# MP2019_LDO_5V.net
KiCad netlist of a schematic drawn in Altium Designer
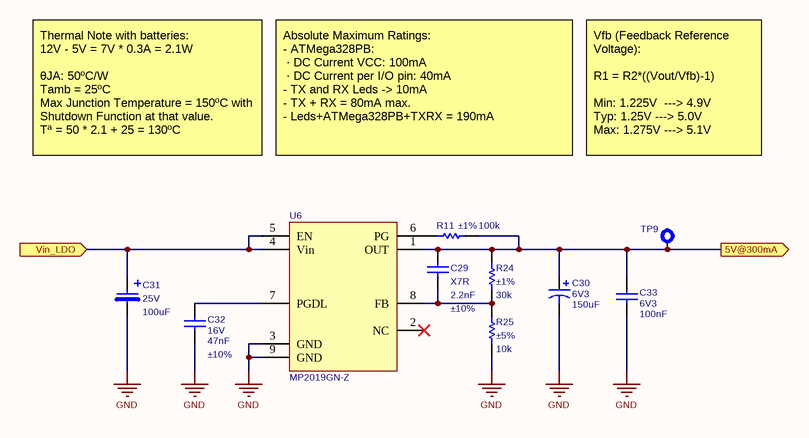
[diagram p0: MP2019_LDO_5V.SchDoc]

(export (version "E")
  (design (tool "Eeschema 10.0.6"))
  (components
    (comp (ref "C29")
      (value "C0402_2.2nF_16V_±10%")
      (footprint "C0402")
      (fields
        (field (name "DIELECTRIC") "X7R")
        (field (name "VOLTAGE") "16V")
        (field (name "CAPACITANCE") "2.2nF")
        (field (name "TOLERANCE") "±10%")
        (field (name "MANUFACTURER") "Kemet")
      )
      (libsource (lib "BQ Vault") (part "Capacitor"))
    )
    (comp (ref "C30")
      (value "150uF_6V3_±20%")
      (footprint "CASE_B_3528-1411")
      (fields
        (field (name "VOLTAGE") "6V3")
        (field (name "CAPACITANCE") "150uF")
        (field (name "TOLERANCE") "±20%")
        (field (name "MANUFACTURER") "Vishay")
      )
      (libsource (lib "BQ Vault") (part "Tantalum"))
    )
    (comp (ref "C31")
      (value "Cap_Al_100uF_25V")
      (footprint "CASE_D_7.7")
      (fields
        (field (name "VOLTAGE") "25V")
        (field (name "CAPACITANCE") "100uF")
        (field (name "MANUFACTURER") "Panasonic")
      )
      (libsource (lib "BQ Vault") (part "Electrolytic"))
    )
    (comp (ref "C32")
      (value "C0402_47nF_16V_±10%")
      (footprint "C0402")
      (fields
        (field (name "VOLTAGE") "16V")
        (field (name "CAPACITANCE") "47nF")
        (field (name "TOLERANCE") "±10%")
        (field (name "MANUFACTURER") "Kemet")
      )
      (libsource (lib "BQ Vault") (part "Capacitor"))
    )
    (comp (ref "C33")
      (value "C0402_100nF_6V3_±10%")
      (footprint "C0402")
      (fields
        (field (name "VOLTAGE") "6V3")
        (field (name "CAPACITANCE") "100nF")
        (field (name "TOLERANCE") "±10%")
        (field (name "MANUFACTURER") "Kemet")
      )
      (libsource (lib "BQ Vault") (part "Capacitor"))
    )
    (comp (ref "R11")
      (value "R0402_100k_0.063W_±1%")
      (footprint "R0402")
      (fields
        (field (name "TOLERANCE") "±1%")
        (field (name "POWER") "0.063W")
        (field (name "RESISTANCE") "100k")
        (field (name "MANUFACTURER") "Vishay")
      )
      (libsource (lib "BQ Vault") (part "Resistor"))
    )
    (comp (ref "R24")
      (value "R0402_30k_0.063W_±1%")
      (footprint "R0402")
      (fields
        (field (name "TOLERANCE") "±1%")
        (field (name "POWER") "0.063W")
        (field (name "RESISTANCE") "30k")
        (field (name "MANUFACTURER") "Vishay")
      )
      (libsource (lib "BQ Vault") (part "Resistor"))
    )
    (comp (ref "R25")
      (value "R0402_10k_0.063W_±5%")
      (footprint "R0402")
      (fields
        (field (name "TOLERANCE") "±5%")
        (field (name "POWER") "0.063W")
        (field (name "RESISTANCE") "10k")
        (field (name "MANUFACTURER") "Vishay")
      )
      (libsource (lib "BQ Vault") (part "CMP-A1692-4"))
    )
    (comp (ref "TP9")
      (value "TP")
      (footprint "TP_POWER")
      (description "Testpoint 0.3mm")
      (fields (field (name "MANUFACTURER") "Oxley") (field (name "PART NUMBER") "TP_POWER"))
      (libsource (lib "BQ Vault") (part "CMP-A2499-3"))
    )
    (comp (ref "U6")
      (value "MP2019GN-Z")
      (footprint "SOIC8 EP")
      (description "LDO Vin: 3-40V Vout: 1.2-15V @300mA")
      (fields (field (name "MANUFACTURER") "Monolithic Power Systems"))
      (libsource (lib "BQ Vault") (part "MP2019"))
    )
  )
  (nets
    (net (code "1") (name "/5V@300mA") (class "Default")
      (node (ref "C29") (pin "1") (pinfunction "1_1") (pintype "passive"))
      (node (ref "C30") (pin "1") (pinfunction "1_1") (pintype "passive"))
      (node (ref "C33") (pin "2") (pinfunction "2_2") (pintype "passive"))
      (node (ref "R11") (pin "1") (pinfunction "1_1") (pintype "passive"))
      (node (ref "R24") (pin "2") (pinfunction "2_2") (pintype "passive"))
      (node (ref "TP9") (pin "1") (pinfunction "1_1") (pintype "passive"))
      (node (ref "U6") (pin "1") (pinfunction "OUT_1") (pintype "passive"))
    )
    (net (code "2") (name "/Vin_LDO") (class "Default")
      (node (ref "C31") (pin "1") (pinfunction "1_1") (pintype "passive"))
      (node (ref "U6") (pin "4") (pinfunction "Vin_4") (pintype "passive"))
      (node (ref "U6") (pin "5") (pinfunction "EN_5") (pintype "passive"))
    )
    (net (code "3") (name "GND") (class "Default")
      (node (ref "C30") (pin "2") (pinfunction "2_2") (pintype "passive"))
      (node (ref "C31") (pin "2") (pinfunction "2_2") (pintype "passive"))
      (node (ref "C32") (pin "1") (pinfunction "1_1") (pintype "passive"))
      (node (ref "C33") (pin "1") (pinfunction "1_1") (pintype "passive"))
      (node (ref "R25") (pin "2") (pinfunction "2_2") (pintype "passive"))
      (node (ref "U6") (pin "3") (pinfunction "GND_3") (pintype "passive"))
      (node (ref "U6") (pin "9") (pinfunction "GND_9") (pintype "passive"))
    )
    (net (code "4") (name "Net-(U6-FB)") (class "Default")
      (node (ref "C29") (pin "2") (pinfunction "2_2") (pintype "passive"))
      (node (ref "R24") (pin "1") (pinfunction "1_1") (pintype "passive"))
      (node (ref "R25") (pin "1") (pinfunction "1_1") (pintype "passive"))
      (node (ref "U6") (pin "8") (pinfunction "FB_8") (pintype "passive"))
    )
    (net (code "5") (name "Net-(U6-PG)") (class "Default")
      (node (ref "R11") (pin "2") (pinfunction "2_2") (pintype "passive"))
      (node (ref "U6") (pin "6") (pinfunction "PG_6") (pintype "passive"))
    )
    (net (code "6") (name "Net-(U6-PGDL)") (class "Default")
      (node (ref "C32") (pin "2") (pinfunction "2_2") (pintype "passive"))
      (node (ref "U6") (pin "7") (pinfunction "PGDL_7") (pintype "passive"))
    )
    (net (code "7") (name "unconnected-(U6-NC-Pad2)") (class "Default")
      (node (ref "U6") (pin "2") (pinfunction "NC_2") (pintype "passive+no_connect"))
    )
  )
)
